# 05-Alarm.net
KiCad netlist of a schematic drawn in Altium Designer
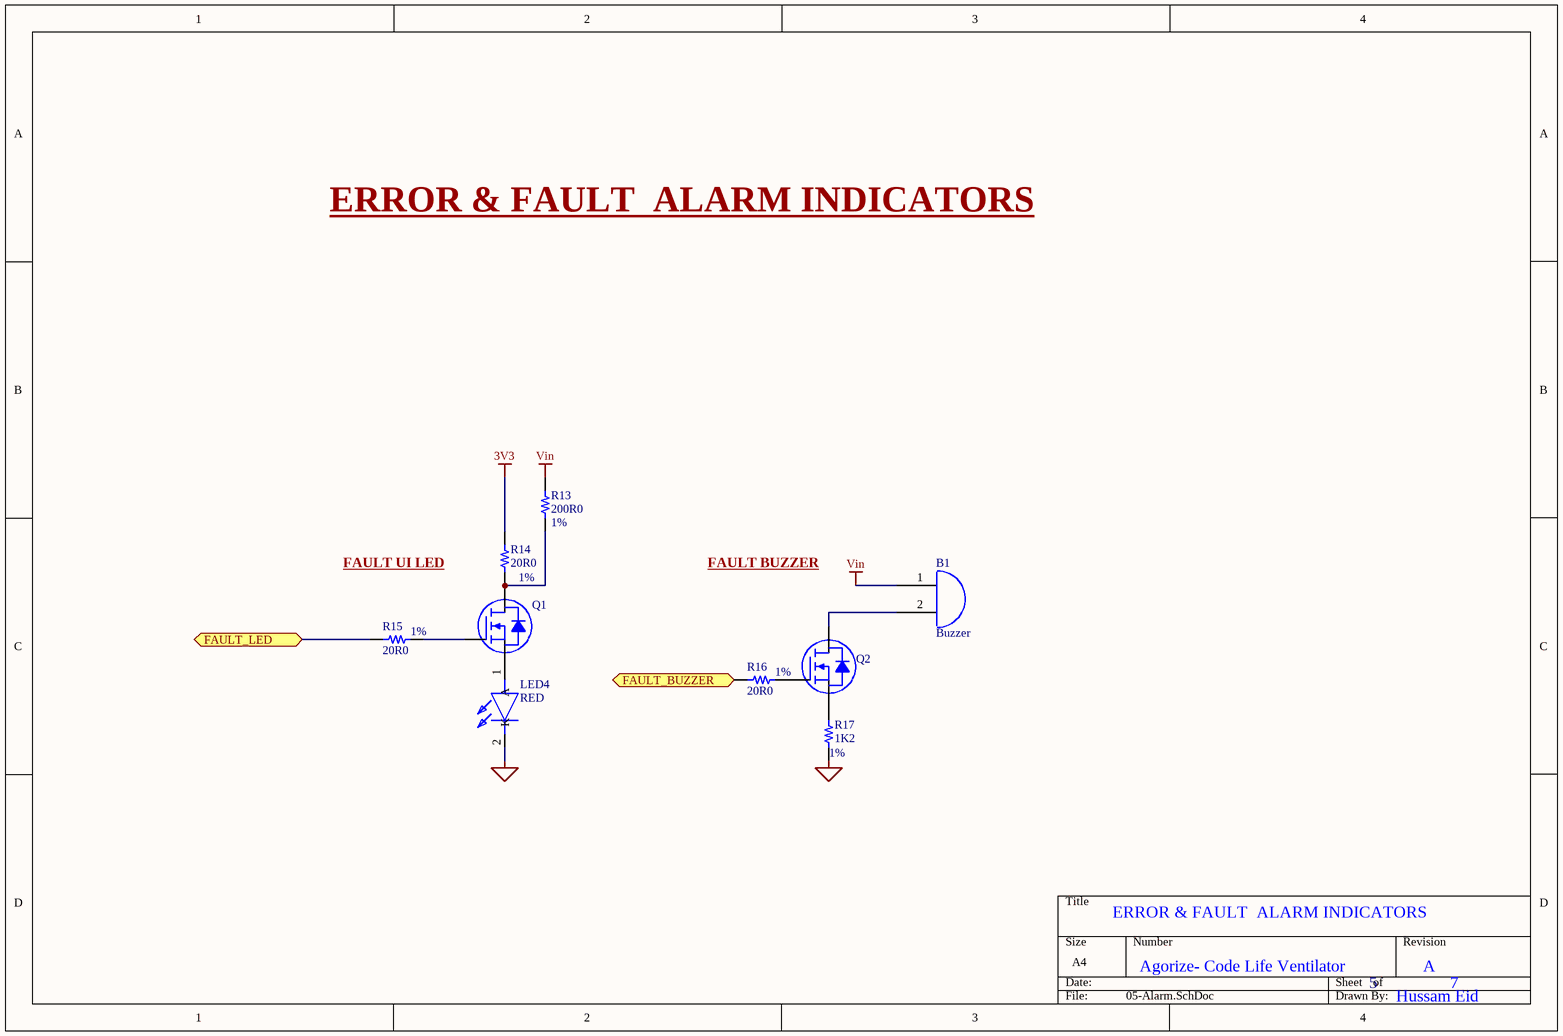
[diagram p0: 05-Alarm.SchDoc]

(export (version "E")
  (design (tool "Eeschema 10.0.6"))
  (components
    (comp (ref "B1")
      (value "Buzzer")
      (footprint "Buzzer")
      (description "BUZZER, 16.5 MM, 6.7 MM DEEP, P,")
      (libsource (lib "Schlib1") (part "Buzzer"))
    )
    (comp (ref "LED4")
      (value "RED")
      (footprint "QBHP686IWKCW")
      (description "Red 620nm LED Indication - Discrete 2.4V 1113 (2835 Metric)")
      (libsource (lib "*") (part "QBHP686-IWK-CW"))
    )
    (comp (ref "Q1")
      (value "~")
      (footprint "SOTFL50P160X70-3N")
      (description "MOSFET N-CH 60V 300MA SOT-23")
      (libsource (lib "Celestial Library Database") (part "NXP MOSFET N-CH SOT-23-3"))
    )
    (comp (ref "Q2")
      (value "~")
      (footprint "SOTFL50P160X70-3N")
      (description "MOSFET N-CH 60V 300MA SOT-23")
      (libsource (lib "Celestial Library Database") (part "NXP MOSFET N-CH SOT-23-3"))
    )
    (comp (ref "R13")
      (value "200R0")
      (footprint "RES 1206/3216")
      (description "RES SMD 10K OHM 1% 1/4W 1206")
      (fields (field (name "TOLERANCE") "1%"))
      (libsource (lib "Celestial Library Database") (part "Resistor"))
    )
    (comp (ref "R14")
      (value "20R0")
      (footprint "RES 1206/3216")
      (description "RES 20 OHM 1% 1/2W 1206")
      (fields (field (name "TOLERANCE") "1%"))
      (libsource (lib "Celestial Library Database") (part "Resistor"))
    )
    (comp (ref "R15")
      (value "20R0")
      (footprint "RES 1206/3216")
      (description "RES 20 OHM 1% 1/2W 1206")
      (fields (field (name "TOLERANCE") "1%"))
      (libsource (lib "Celestial Library Database") (part "Resistor"))
    )
    (comp (ref "R16")
      (value "20R0")
      (footprint "RES 1206/3216")
      (description "RES 20 OHM 1% 1/2W 1206")
      (fields (field (name "TOLERANCE") "1%"))
      (libsource (lib "Celestial Library Database") (part "Resistor"))
    )
    (comp (ref "R17")
      (value "1K2")
      (footprint "RES 1206/3216")
      (description "RES SMD 1.2K OHM 1% 1/4W 1206")
      (fields (field (name "TOLERANCE") "1%"))
      (libsource (lib "Celestial Library Database") (part "Resistor"))
    )
  )
  (nets
    (net (code "1") (name "/FAULT_BUZZER") (class "Default")
      (node (ref "R16") (pin "2") (pinfunction "2_2") (pintype "passive"))
    )
    (net (code "2") (name "/FAULT_LED") (class "Default")
      (node (ref "R15") (pin "2") (pinfunction "2_2") (pintype "passive"))
    )
    (net (code "3") (name "3V3") (class "Default")
      (node (ref "R14") (pin "2") (pinfunction "2_2") (pintype "passive"))
    )
    (net (code "4") (name "COM") (class "Default")
      (node (ref "LED4") (pin "2") (pinfunction "K_2") (pintype "passive"))
      (node (ref "R17") (pin "2") (pinfunction "2_2") (pintype "passive"))
    )
    (net (code "5") (name "Net-(LED4-A)") (class "Default")
      (node (ref "LED4") (pin "1") (pinfunction "A_1") (pintype "passive"))
      (node (ref "Q1") (pin "1") (pinfunction "S_1") (pintype "passive"))
    )
    (net (code "6") (name "Net-(Q1-D)") (class "Default")
      (node (ref "Q1") (pin "3") (pinfunction "D_3") (pintype "passive"))
      (node (ref "R13") (pin "1") (pinfunction "1_1") (pintype "passive"))
      (node (ref "R14") (pin "1") (pinfunction "1_1") (pintype "passive"))
    )
    (net (code "7") (name "Net-(Q1-G)") (class "Default")
      (node (ref "Q1") (pin "2") (pinfunction "G_2") (pintype "passive"))
      (node (ref "R15") (pin "1") (pinfunction "1_1") (pintype "passive"))
    )
    (net (code "8") (name "Net-(Q2-D)") (class "Default")
      (node (ref "B1") (pin "2") (pinfunction "2_2") (pintype "passive"))
      (node (ref "Q2") (pin "3") (pinfunction "D_3") (pintype "passive"))
    )
    (net (code "9") (name "Net-(Q2-G)") (class "Default")
      (node (ref "Q2") (pin "2") (pinfunction "G_2") (pintype "passive"))
      (node (ref "R16") (pin "1") (pinfunction "1_1") (pintype "passive"))
    )
    (net (code "10") (name "Net-(Q2-S)") (class "Default")
      (node (ref "Q2") (pin "1") (pinfunction "S_1") (pintype "passive"))
      (node (ref "R17") (pin "1") (pinfunction "1_1") (pintype "passive"))
    )
    (net (code "11") (name "Vin") (class "Default")
      (node (ref "B1") (pin "1") (pinfunction "1_1") (pintype "passive"))
      (node (ref "R13") (pin "2") (pinfunction "2_2") (pintype "passive"))
    )
  )
)
